# 1-Schematic_Arduino_uno.net
KiCad netlist of a schematic drawn in EasyEDA
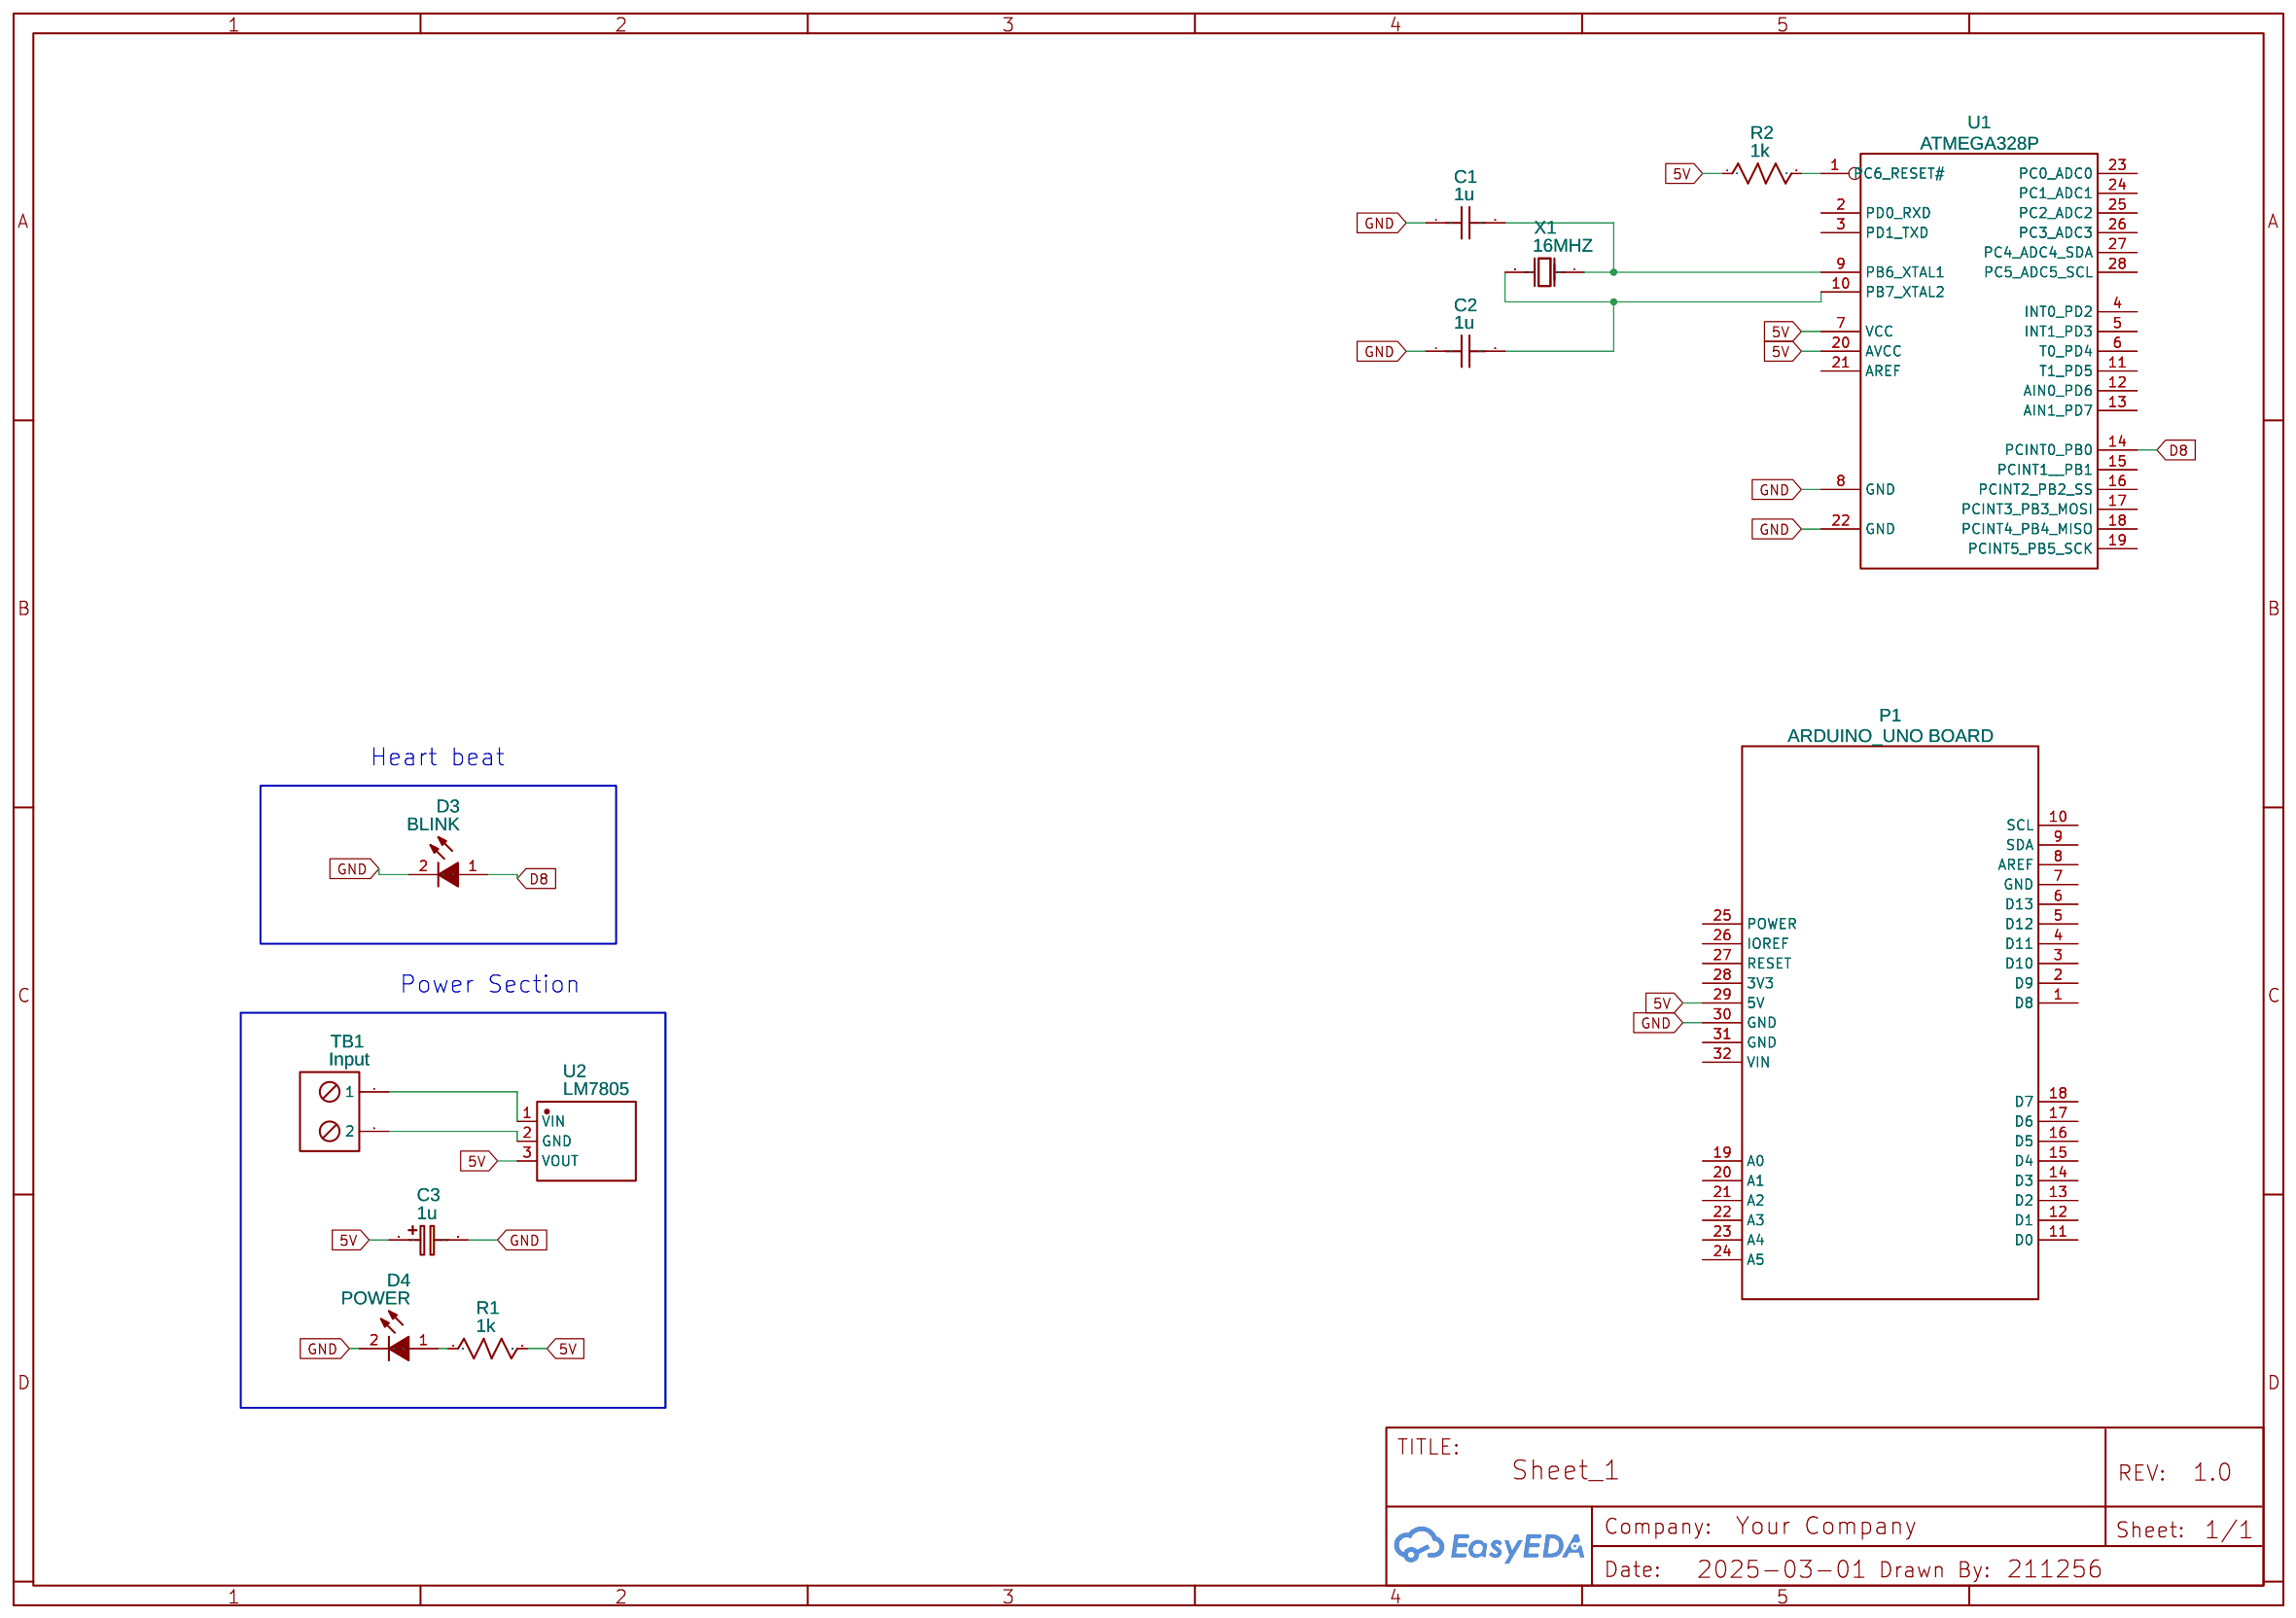
[diagram p0: schematic sheet]

(export (version "E")
  (design (tool "Eeschema 10.0.6"))
  (components
    (comp (ref "C1") (value "1u") (libsource (lib "") (part "C_RAD-0.1_US")))
    (comp (ref "C2") (value "1u") (libsource (lib "") (part "C_RAD-0.1_US")))
    (comp (ref "C3") (value "1u") (libsource (lib "") (part "CE_TH_D3.0×F1.5_EU")))
    (comp (ref "D3")
      (value "BLINK")
      (fields (field (name "Manufacturer Part") "5600") (field (name "Manufacturer") "VccLite"))
      (libsource (lib "") (part "LED 5x7 DIP"))
    )
    (comp (ref "D4")
      (value "POWER")
      (fields (field (name "Manufacturer Part") "5600") (field (name "Manufacturer") "VccLite"))
      (libsource (lib "") (part "LED 5x7 DIP"))
    )
    (comp (ref "P1") (value "ARDUINO_UNO BOARD") (libsource (lib "") (part "ARDUINO_UNO BOARD COPY")))
    (comp (ref "R1") (value "1k") (libsource (lib "") (part "R_AXIAL-0.3_US")))
    (comp (ref "R2") (value "1k") (libsource (lib "") (part "R_AXIAL-0.3_US")))
    (comp (ref "TB1") (value "Input") (libsource (lib "") (part "TBLOCK-X2")))
    (comp (ref "U1")
      (value "ATMEGA328P")
      (fields (field (name "Manufacturer Part") "ATMEGA328P-PU") (field (name "Manufacturer") "MICROCHIP"))
      (libsource (lib "") (part "ATMEGA328P-PU GT"))
    )
    (comp (ref "U2")
      (value "LM7805")
      (fields (field (name "Manufacturer Part") "LM7805G-TF3-T") (field (name "Manufacturer") "UTC(友顺)"))
      (libsource (lib "") (part "LM7805G-TF3-T"))
    )
    (comp (ref "X1")
      (value "16MHZ")
      (fields (field (name "Manufacturer Part") "X49SD16MSD2SC") (field (name "Manufacturer") "YXC"))
      (libsource (lib "") (part "CRYSTAL OSCILLATOR-16MHZ"))
    )
  )
  (nets
    (net (code "1") (name "5V") (class "Default")
      (node (ref "C3") (pin "1") (pinfunction "1_1") (pintype "unspecified"))
      (node (ref "P1") (pin "29") (pinfunction "5V_29") (pintype "unspecified"))
      (node (ref "R1") (pin "2") (pinfunction "2_2") (pintype "unspecified"))
      (node (ref "R2") (pin "1") (pinfunction "1_1") (pintype "unspecified"))
      (node (ref "U1") (pin "20") (pinfunction "AVCC_20") (pintype "passive"))
      (node (ref "U1") (pin "7") (pinfunction "VCC_7") (pintype "passive"))
      (node (ref "U2") (pin "3") (pinfunction "VOUT_3") (pintype "unspecified"))
    )
    (net (code "2") (name "D8") (class "Default")
      (node (ref "D3") (pin "1") (pinfunction "A_1") (pintype "input"))
      (node (ref "U1") (pin "14") (pinfunction "PCINT0_PB0_14") (pintype "bidirectional"))
    )
    (net (code "3") (name "GND") (class "Default")
      (node (ref "C1") (pin "1") (pinfunction "1_1") (pintype "unspecified"))
      (node (ref "C2") (pin "1") (pinfunction "1_1") (pintype "unspecified"))
      (node (ref "C3") (pin "2") (pinfunction "2_2") (pintype "unspecified"))
      (node (ref "D3") (pin "2") (pinfunction "K_2") (pintype "input"))
      (node (ref "D4") (pin "2") (pinfunction "K_2") (pintype "input"))
      (node (ref "P1") (pin "30") (pinfunction "GND_30") (pintype "unspecified"))
      (node (ref "U1") (pin "22") (pinfunction "GND_22") (pintype "passive"))
      (node (ref "U1") (pin "8") (pinfunction "GND_8") (pintype "passive"))
    )
    (net (code "4") (name "Net-(D4-A)") (class "Default")
      (node (ref "D4") (pin "1") (pinfunction "A_1") (pintype "input"))
      (node (ref "R1") (pin "1") (pinfunction "1_1") (pintype "unspecified"))
    )
    (net (code "5") (name "Net-(U1-PB6_XTAL1)") (class "Default")
      (node (ref "C1") (pin "2") (pinfunction "2_2") (pintype "unspecified"))
      (node (ref "U1") (pin "9") (pinfunction "PB6_XTAL1_9") (pintype "bidirectional"))
      (node (ref "X1") (pin "1") (pinfunction "OSC1_1") (pintype "unspecified"))
    )
    (net (code "6") (name "Net-(U1-PB7_XTAL2)") (class "Default")
      (node (ref "C2") (pin "2") (pinfunction "2_2") (pintype "unspecified"))
      (node (ref "U1") (pin "10") (pinfunction "PB7_XTAL2_10") (pintype "bidirectional"))
      (node (ref "X1") (pin "2") (pinfunction "OSC2_2") (pintype "unspecified"))
    )
    (net (code "7") (name "Net-(U1-PC6_RESET#)") (class "Default")
      (node (ref "R2") (pin "2") (pinfunction "2_2") (pintype "unspecified"))
      (node (ref "U1") (pin "1") (pinfunction "PC6_RESET#_1") (pintype "bidirectional"))
    )
    (net (code "8") (name "Net-(U2-GND)") (class "Default")
      (node (ref "TB1") (pin "2") (pinfunction "2_2") (pintype "unspecified"))
      (node (ref "U2") (pin "2") (pinfunction "GND_2") (pintype "unspecified"))
    )
    (net (code "9") (name "Net-(U2-VIN)") (class "Default")
      (node (ref "TB1") (pin "1") (pinfunction "1_1") (pintype "unspecified"))
      (node (ref "U2") (pin "1") (pinfunction "VIN_1") (pintype "unspecified"))
    )
    (net (code "10") (name "unconnected-(P1-3V3-Pad28)") (class "Default")
      (node (ref "P1") (pin "28") (pinfunction "3V3_28") (pintype "unspecified"))
    )
    (net (code "11") (name "unconnected-(P1-A0-Pad19)") (class "Default")
      (node (ref "P1") (pin "19") (pinfunction "A0_19") (pintype "unspecified"))
    )
    (net (code "12") (name "unconnected-(P1-A1-Pad20)") (class "Default")
      (node (ref "P1") (pin "20") (pinfunction "A1_20") (pintype "unspecified"))
    )
    (net (code "13") (name "unconnected-(P1-A2-Pad21)") (class "Default")
      (node (ref "P1") (pin "21") (pinfunction "A2_21") (pintype "unspecified"))
    )
    (net (code "14") (name "unconnected-(P1-A3-Pad22)") (class "Default")
      (node (ref "P1") (pin "22") (pinfunction "A3_22") (pintype "unspecified"))
    )
    (net (code "15") (name "unconnected-(P1-A4-Pad23)") (class "Default")
      (node (ref "P1") (pin "23") (pinfunction "A4_23") (pintype "unspecified"))
    )
    (net (code "16") (name "unconnected-(P1-A5-Pad24)") (class "Default")
      (node (ref "P1") (pin "24") (pinfunction "A5_24") (pintype "unspecified"))
    )
    (net (code "17") (name "unconnected-(P1-AREF-Pad8)") (class "Default")
      (node (ref "P1") (pin "8") (pinfunction "AREF_8") (pintype "unspecified"))
    )
    (net (code "18") (name "unconnected-(P1-D0-Pad11)") (class "Default")
      (node (ref "P1") (pin "11") (pinfunction "D0_11") (pintype "unspecified"))
    )
    (net (code "19") (name "unconnected-(P1-D1-Pad12)") (class "Default")
      (node (ref "P1") (pin "12") (pinfunction "D1_12") (pintype "unspecified"))
    )
    (net (code "20") (name "unconnected-(P1-D2-Pad13)") (class "Default")
      (node (ref "P1") (pin "13") (pinfunction "D2_13") (pintype "unspecified"))
    )
    (net (code "21") (name "unconnected-(P1-D3-Pad14)") (class "Default")
      (node (ref "P1") (pin "14") (pinfunction "D3_14") (pintype "unspecified"))
    )
    (net (code "22") (name "unconnected-(P1-D4-Pad15)") (class "Default")
      (node (ref "P1") (pin "15") (pinfunction "D4_15") (pintype "unspecified"))
    )
    (net (code "23") (name "unconnected-(P1-D5-Pad16)") (class "Default")
      (node (ref "P1") (pin "16") (pinfunction "D5_16") (pintype "unspecified"))
    )
    (net (code "24") (name "unconnected-(P1-D6-Pad17)") (class "Default")
      (node (ref "P1") (pin "17") (pinfunction "D6_17") (pintype "unspecified"))
    )
    (net (code "25") (name "unconnected-(P1-D7-Pad18)") (class "Default")
      (node (ref "P1") (pin "18") (pinfunction "D7_18") (pintype "unspecified"))
    )
    (net (code "26") (name "unconnected-(P1-D8-Pad1)") (class "Default")
      (node (ref "P1") (pin "1") (pinfunction "D8_1") (pintype "unspecified"))
    )
    (net (code "27") (name "unconnected-(P1-D9-Pad2)") (class "Default")
      (node (ref "P1") (pin "2") (pinfunction "D9_2") (pintype "unspecified"))
    )
    (net (code "28") (name "unconnected-(P1-D10-Pad3)") (class "Default")
      (node (ref "P1") (pin "3") (pinfunction "D10_3") (pintype "unspecified"))
    )
    (net (code "29") (name "unconnected-(P1-D11-Pad4)") (class "Default")
      (node (ref "P1") (pin "4") (pinfunction "D11_4") (pintype "unspecified"))
    )
    (net (code "30") (name "unconnected-(P1-D12-Pad5)") (class "Default")
      (node (ref "P1") (pin "5") (pinfunction "D12_5") (pintype "unspecified"))
    )
    (net (code "31") (name "unconnected-(P1-D13-Pad6)") (class "Default")
      (node (ref "P1") (pin "6") (pinfunction "D13_6") (pintype "unspecified"))
    )
    (net (code "32") (name "unconnected-(P1-GND-Pad7)") (class "Default")
      (node (ref "P1") (pin "7") (pinfunction "GND_7") (pintype "unspecified"))
    )
    (net (code "33") (name "unconnected-(P1-GND-Pad31)") (class "Default")
      (node (ref "P1") (pin "31") (pinfunction "GND_31") (pintype "unspecified"))
    )
    (net (code "34") (name "unconnected-(P1-IOREF-Pad26)") (class "Default")
      (node (ref "P1") (pin "26") (pinfunction "IOREF_26") (pintype "unspecified"))
    )
    (net (code "35") (name "unconnected-(P1-POWER-Pad25)") (class "Default")
      (node (ref "P1") (pin "25") (pinfunction "POWER_25") (pintype "unspecified"))
    )
    (net (code "36") (name "unconnected-(P1-RESET-Pad27)") (class "Default")
      (node (ref "P1") (pin "27") (pinfunction "RESET_27") (pintype "unspecified"))
    )
    (net (code "37") (name "unconnected-(P1-SCL-Pad10)") (class "Default")
      (node (ref "P1") (pin "10") (pinfunction "SCL_10") (pintype "unspecified"))
    )
    (net (code "38") (name "unconnected-(P1-SDA-Pad9)") (class "Default")
      (node (ref "P1") (pin "9") (pinfunction "SDA_9") (pintype "unspecified"))
    )
    (net (code "39") (name "unconnected-(P1-VIN-Pad32)") (class "Default")
      (node (ref "P1") (pin "32") (pinfunction "VIN_32") (pintype "unspecified"))
    )
    (net (code "40") (name "unconnected-(U1-AIN0_PD6-Pad12)") (class "Default")
      (node (ref "U1") (pin "12") (pinfunction "AIN0_PD6_12") (pintype "bidirectional"))
    )
    (net (code "41") (name "unconnected-(U1-AIN1_PD7-Pad13)") (class "Default")
      (node (ref "U1") (pin "13") (pinfunction "AIN1_PD7_13") (pintype "bidirectional"))
    )
    (net (code "42") (name "unconnected-(U1-AREF-Pad21)") (class "Default")
      (node (ref "U1") (pin "21") (pinfunction "AREF_21") (pintype "passive"))
    )
    (net (code "43") (name "unconnected-(U1-INT0_PD2-Pad4)") (class "Default")
      (node (ref "U1") (pin "4") (pinfunction "INT0_PD2_4") (pintype "bidirectional"))
    )
    (net (code "44") (name "unconnected-(U1-INT1_PD3-Pad5)") (class "Default")
      (node (ref "U1") (pin "5") (pinfunction "INT1_PD3_5") (pintype "bidirectional"))
    )
    (net (code "45") (name "unconnected-(U1-PC0_ADC0-Pad23)") (class "Default")
      (node (ref "U1") (pin "23") (pinfunction "PC0_ADC0_23") (pintype "bidirectional"))
    )
    (net (code "46") (name "unconnected-(U1-PC1_ADC1-Pad24)") (class "Default")
      (node (ref "U1") (pin "24") (pinfunction "PC1_ADC1_24") (pintype "bidirectional"))
    )
    (net (code "47") (name "unconnected-(U1-PC2_ADC2-Pad25)") (class "Default")
      (node (ref "U1") (pin "25") (pinfunction "PC2_ADC2_25") (pintype "bidirectional"))
    )
    (net (code "48") (name "unconnected-(U1-PC3_ADC3-Pad26)") (class "Default")
      (node (ref "U1") (pin "26") (pinfunction "PC3_ADC3_26") (pintype "bidirectional"))
    )
    (net (code "49") (name "unconnected-(U1-PC4_ADC4_SDA-Pad27)") (class "Default")
      (node (ref "U1") (pin "27") (pinfunction "PC4_ADC4_SDA_27") (pintype "bidirectional"))
    )
    (net (code "50") (name "unconnected-(U1-PC5_ADC5_SCL-Pad28)") (class "Default")
      (node (ref "U1") (pin "28") (pinfunction "PC5_ADC5_SCL_28") (pintype "bidirectional"))
    )
    (net (code "51") (name "unconnected-(U1-PCINT1__PB1-Pad15)") (class "Default")
      (node (ref "U1") (pin "15") (pinfunction "PCINT1__PB1_15") (pintype "bidirectional"))
    )
    (net (code "52") (name "unconnected-(U1-PCINT2_PB2_SS-Pad16)") (class "Default")
      (node (ref "U1") (pin "16") (pinfunction "PCINT2_PB2_SS_16") (pintype "bidirectional"))
    )
    (net (code "53") (name "unconnected-(U1-PCINT3_PB3_MOSI-Pad17)") (class "Default")
      (node (ref "U1") (pin "17") (pinfunction "PCINT3_PB3_MOSI_17") (pintype "bidirectional"))
    )
    (net (code "54") (name "unconnected-(U1-PCINT4_PB4_MISO-Pad18)") (class "Default")
      (node (ref "U1") (pin "18") (pinfunction "PCINT4_PB4_MISO_18") (pintype "bidirectional"))
    )
    (net (code "55") (name "unconnected-(U1-PCINT5_PB5_SCK-Pad19)") (class "Default")
      (node (ref "U1") (pin "19") (pinfunction "PCINT5_PB5_SCK_19") (pintype "bidirectional"))
    )
    (net (code "56") (name "unconnected-(U1-PD0_RXD-Pad2)") (class "Default")
      (node (ref "U1") (pin "2") (pinfunction "PD0_RXD_2") (pintype "bidirectional"))
    )
    (net (code "57") (name "unconnected-(U1-PD1_TXD-Pad3)") (class "Default")
      (node (ref "U1") (pin "3") (pinfunction "PD1_TXD_3") (pintype "bidirectional"))
    )
    (net (code "58") (name "unconnected-(U1-T0_PD4-Pad6)") (class "Default")
      (node (ref "U1") (pin "6") (pinfunction "T0_PD4_6") (pintype "bidirectional"))
    )
    (net (code "59") (name "unconnected-(U1-T1_PD5-Pad11)") (class "Default")
      (node (ref "U1") (pin "11") (pinfunction "T1_PD5_11") (pintype "bidirectional"))
    )
  )
)
